# PID.net
KiCad netlist of a schematic drawn in Altium Designer
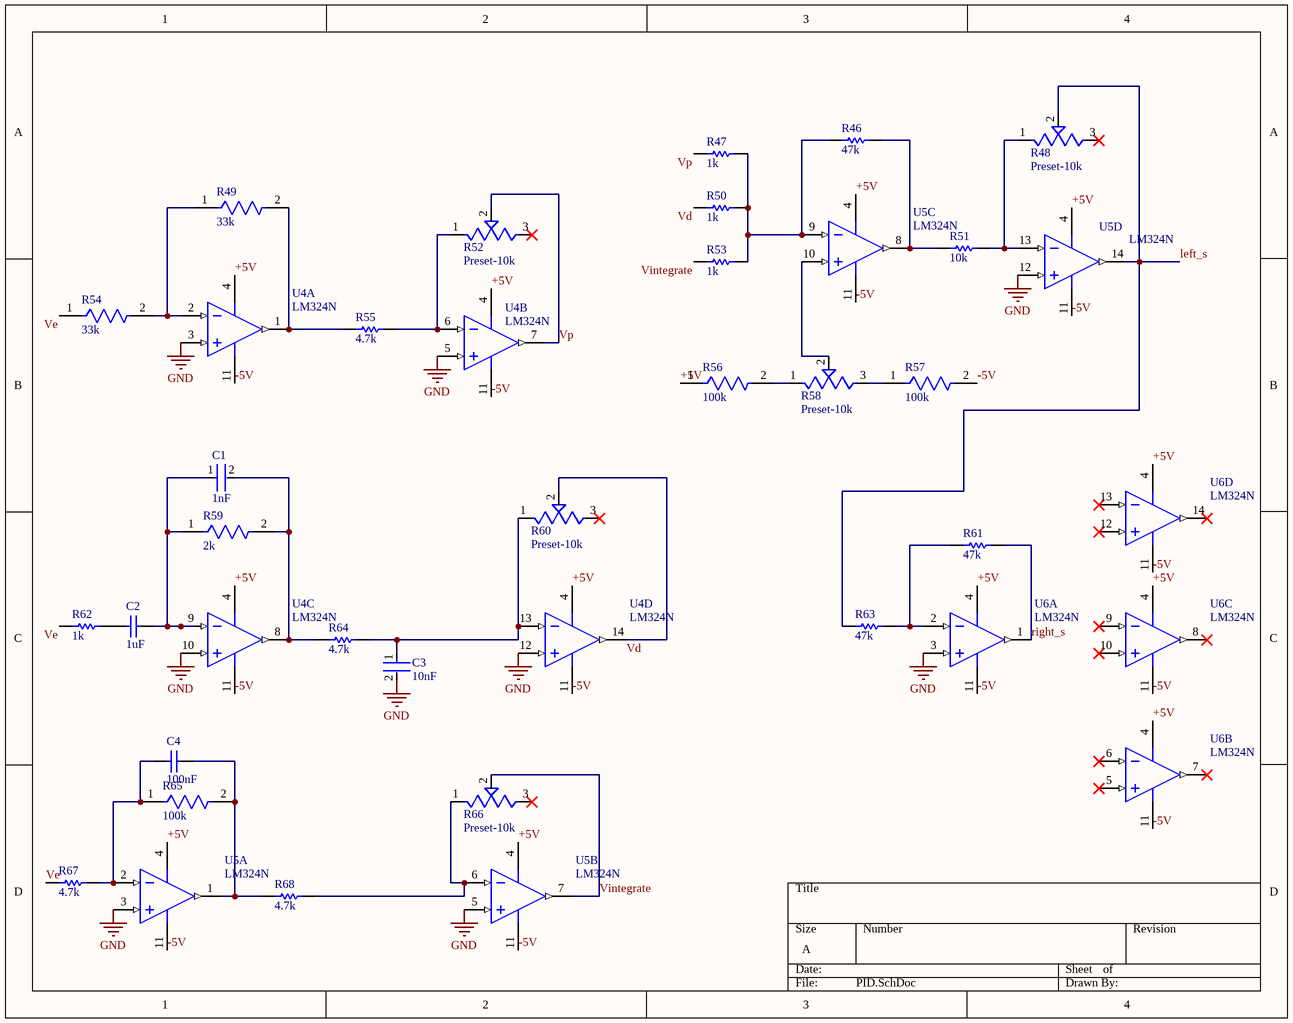
[diagram p0: PID.SchDoc]

(export (version "E")
  (design (tool "Eeschema 10.0.6"))
  (components
    (comp (ref "C1")
      (value "1nF")
      (footprint "FP-CL21-IPC_B")
      (description "CL21 Series 0805 1nF 50V ±10% Tolerance X7R Multilayer Ceramic Chip Capacitor; CL21B102KBANNNC")
      (fields (field (name "TOLERANCE") "10%") (field (name "VOLTAGE") "50V"))
      (libsource (lib "Capacitors") (part "1nF"))
    )
    (comp (ref "C2")
      (value "1uF")
      (footprint "CAPC2013X135X45ML10T25")
      (fields (field (name "MANUFACTURER") "Murata"))
      (libsource (lib "Capacitors") (part "1uF"))
    )
    (comp (ref "C3")
      (value "10nF")
      (footprint "FP-C0805C-DN-MFG")
      (description "CAP CER 10000PF 50V X7R 0805; C0805C103K5RACTU")
      (fields (field (name "MANUFACTURER PART NUMBER") "C0805C103K5RACTU") (field (name "TOLERANCE") "0.1"))
      (libsource (lib "Capacitors") (part "10nF"))
    )
    (comp (ref "C4")
      (value "100nF")
      (footprint "CAPC2013X135X45ML10T25")
      (fields
        (field (name "VOLTAGE") "50V")
        (field (name "TOLERANCE") "10%")
        (field (name "MANUFACTURER") "Murata")
      )
      (libsource (lib "Capacitors") (part "100nF"))
    )
    (comp (ref "R46")
      (value "47k")
      (footprint "RESC2013X60X35NL10T20")
      (fields (field (name "MANUFACTURER") "Yageo"))
      (libsource (lib "Resistors") (part "47k"))
    )
    (comp (ref "R47")
      (value "1k")
      (footprint "RESC2013X60X35ML10T20")
      (fields (field (name "TOLERANCE") "1%") (field (name "MANUFACTURER") "Yageo"))
      (libsource (lib "Resistors") (part "1k"))
    )
    (comp (ref "R48")
      (value "Preset-10k")
      (footprint "TRIM_3306F-1-103")
      (description "TRIMMER - 6MM ROUND, SINGLE-TURN,CERMET, 10K OHMS ¦ Bourns 3306F-1-103")
      (fields (field (name "MF") "Bourns") (field (name "MP") "3306F-1-103"))
      (libsource (lib "3306F-1-103") (part "Preset"))
    )
    (comp (ref "R49")
      (value "33k")
      (footprint "FP-CRCW0805-e3-IPC_B")
      (description "RES Thick Film, 33kΩ, 1%, 0.125W, 100ppm/°C, 0805; CRCW080533K0FKEA")
      (fields (field (name "TOLERANCE") "1%"))
      (libsource (lib "Resistors") (part "33k"))
    )
    (comp (ref "R50")
      (value "1k")
      (footprint "RESC2013X60X35ML10T20")
      (fields (field (name "TOLERANCE") "1%") (field (name "MANUFACTURER") "Yageo"))
      (libsource (lib "Resistors") (part "1k"))
    )
    (comp (ref "R51")
      (value "10k")
      (footprint "RESC2013X60X35NL10T20")
      (fields (field (name "MANUFACTURER") "Yageo"))
      (libsource (lib "Resistors") (part "10k"))
    )
    (comp (ref "R52")
      (value "Preset-10k")
      (footprint "TRIM_3306F-1-103")
      (description "TRIMMER - 6MM ROUND, SINGLE-TURN,CERMET, 10K OHMS ¦ Bourns 3306F-1-103")
      (fields (field (name "MF") "Bourns") (field (name "MP") "3306F-1-103"))
      (libsource (lib "3306F-1-103") (part "Preset"))
    )
    (comp (ref "R53")
      (value "1k")
      (footprint "RESC2013X60X35ML10T20")
      (fields (field (name "TOLERANCE") "1%") (field (name "MANUFACTURER") "Yageo"))
      (libsource (lib "Resistors") (part "1k"))
    )
    (comp (ref "R54")
      (value "33k")
      (footprint "FP-CRCW0805-e3-IPC_B")
      (description "RES Thick Film, 33kΩ, 1%, 0.125W, 100ppm/°C, 0805; CRCW080533K0FKEA")
      (fields (field (name "TOLERANCE") "1%"))
      (libsource (lib "Resistors") (part "33k"))
    )
    (comp (ref "R55")
      (value "4.7k")
      (footprint "YAGO-RC0805_M")
      (fields
        (field (name "TOLERANCE") "+/- 1%")
        (field (name "PARTNUMBER") "RC0805FR-074K7L")
        (field (name "POWER") "0.125 W")
      )
      (libsource (lib "Resistors") (part "4.7k"))
    )
    (comp (ref "R56")
      (value "100k")
      (footprint "FP-RC0805-0_6-IPC_C")
      (description "RES 100K OHM 1% 1/8W 0805; RC0805FR-07100KL")
      (fields (field (name "TOLERANCE") "1%"))
      (libsource (lib "Resistors") (part "100k"))
    )
    (comp (ref "R57")
      (value "100k")
      (footprint "FP-RC0805-0_6-IPC_C")
      (description "RES 100K OHM 1% 1/8W 0805; RC0805FR-07100KL")
      (fields (field (name "TOLERANCE") "1%"))
      (libsource (lib "Resistors") (part "100k"))
    )
    (comp (ref "R58")
      (value "Preset-10k")
      (footprint "TRIM_3306F-1-103")
      (description "TRIMMER - 6MM ROUND, SINGLE-TURN,CERMET, 10K OHMS ¦ Bourns 3306F-1-103")
      (fields (field (name "MF") "Bourns") (field (name "MP") "3306F-1-103"))
      (libsource (lib "3306F-1-103") (part "Preset"))
    )
    (comp (ref "R59")
      (value "2k")
      (footprint "FP-CRCW0805-e3-IPC_B")
      (description "RES Thick Film, 2kΩ, 1%, 0.125W, 100ppm/°C, 0805; CRCW08052K00FKEA")
      (fields (field (name "TOLERANCE") "1%"))
      (libsource (lib "Resistors") (part "2k"))
    )
    (comp (ref "R60")
      (value "Preset-10k")
      (footprint "TRIM_3306F-1-103")
      (description "TRIMMER - 6MM ROUND, SINGLE-TURN,CERMET, 10K OHMS ¦ Bourns 3306F-1-103")
      (fields (field (name "MF") "Bourns") (field (name "MP") "3306F-1-103"))
      (libsource (lib "3306F-1-103") (part "Preset"))
    )
    (comp (ref "R61")
      (value "47k")
      (footprint "RESC2013X60X35NL10T20")
      (fields (field (name "MANUFACTURER") "Yageo"))
      (libsource (lib "Resistors") (part "47k"))
    )
    (comp (ref "R62")
      (value "1k")
      (footprint "RESC2013X60X35ML10T20")
      (fields (field (name "TOLERANCE") "1%") (field (name "MANUFACTURER") "Yageo"))
      (libsource (lib "Resistors") (part "1k"))
    )
    (comp (ref "R63")
      (value "47k")
      (footprint "RESC2013X60X35NL10T20")
      (fields (field (name "MANUFACTURER") "Yageo"))
      (libsource (lib "Resistors") (part "47k"))
    )
    (comp (ref "R64")
      (value "4.7k")
      (footprint "YAGO-RC0805_M")
      (fields
        (field (name "TOLERANCE") "+/- 1%")
        (field (name "PARTNUMBER") "RC0805FR-074K7L")
        (field (name "POWER") "0.125 W")
      )
      (libsource (lib "Resistors") (part "4.7k"))
    )
    (comp (ref "R65")
      (value "100k")
      (footprint "FP-RC0805-0_6-IPC_C")
      (description "RES 100K OHM 1% 1/8W 0805; RC0805FR-07100KL")
      (fields (field (name "TOLERANCE") "1%"))
      (libsource (lib "Resistors") (part "100k"))
    )
    (comp (ref "R66")
      (value "Preset-10k")
      (footprint "TRIM_3306F-1-103")
      (description "TRIMMER - 6MM ROUND, SINGLE-TURN,CERMET, 10K OHMS ¦ Bourns 3306F-1-103")
      (fields (field (name "MF") "Bourns") (field (name "MP") "3306F-1-103"))
      (libsource (lib "3306F-1-103") (part "Preset"))
    )
    (comp (ref "R67")
      (value "4.7k")
      (footprint "YAGO-RC0805_M")
      (fields
        (field (name "TOLERANCE") "+/- 1%")
        (field (name "PARTNUMBER") "RC0805FR-074K7L")
        (field (name "POWER") "0.125 W")
      )
      (libsource (lib "Resistors") (part "4.7k"))
    )
    (comp (ref "R68")
      (value "4.7k")
      (footprint "YAGO-RC0805_M")
      (fields
        (field (name "TOLERANCE") "+/- 1%")
        (field (name "PARTNUMBER") "RC0805FR-074K7L")
        (field (name "POWER") "0.125 W")
      )
      (libsource (lib "Resistors") (part "4.7k"))
    )
    (comp (ref "U4")
      (value "LM324N")
      (footprint "N0014A")
      (description "Low Power Quad Operational Amplifier, 14-pin MDIP")
      (fields (field (name "MANUFACTURER") "Texas Instruments"))
      (libsource (lib "ICs") (part "LM324N"))
    )
    (comp (ref "U5")
      (value "LM324N")
      (footprint "N0014A")
      (description "Low Power Quad Operational Amplifier, 14-pin MDIP")
      (fields (field (name "MANUFACTURER") "Texas Instruments"))
      (libsource (lib "ICs") (part "LM324N"))
    )
    (comp (ref "U6")
      (value "LM324N")
      (footprint "N0014A")
      (description "Low Power Quad Operational Amplifier, 14-pin MDIP")
      (fields (field (name "MANUFACTURER") "Texas Instruments"))
      (libsource (lib "ICs") (part "LM324N"))
    )
  )
  (nets
    (net (code "1") (name "/+5V") (class "Default")
      (node (ref "R56") (pin "1") (pinfunction "1_1") (pintype "passive"))
      (node (ref "U4") (pin "4") (pinfunction "V+_4") (pintype "power_in"))
      (node (ref "U5") (pin "4") (pinfunction "V+_4") (pintype "power_in"))
      (node (ref "U6") (pin "4") (pinfunction "V+_4") (pintype "power_in"))
    )
    (net (code "2") (name "/-5V") (class "Default")
      (node (ref "R57") (pin "2") (pinfunction "2_2") (pintype "passive"))
      (node (ref "U4") (pin "11") (pinfunction "GND_11") (pintype "power_in"))
      (node (ref "U5") (pin "11") (pinfunction "GND_11") (pintype "power_in"))
      (node (ref "U6") (pin "11") (pinfunction "GND_11") (pintype "power_in"))
    )
    (net (code "3") (name "/Vd") (class "Default")
      (node (ref "R50") (pin "1") (pinfunction "1_1") (pintype "passive"))
      (node (ref "R60") (pin "2") (pinfunction "W_2") (pintype "passive"))
      (node (ref "U4") (pin "14") (pinfunction "OUT4_14") (pintype "output"))
    )
    (net (code "4") (name "/Ve") (class "Default")
      (node (ref "R54") (pin "1") (pinfunction "1_1") (pintype "passive"))
      (node (ref "R62") (pin "1") (pinfunction "1_1") (pintype "passive"))
      (node (ref "R67") (pin "1") (pinfunction "1_1") (pintype "passive"))
    )
    (net (code "5") (name "/Vintegrate") (class "Default")
      (node (ref "R53") (pin "1") (pinfunction "1_1") (pintype "passive"))
      (node (ref "R66") (pin "2") (pinfunction "W_2") (pintype "passive"))
      (node (ref "U5") (pin "7") (pinfunction "OUT2_7") (pintype "output"))
    )
    (net (code "6") (name "/Vp") (class "Default")
      (node (ref "R47") (pin "1") (pinfunction "1_1") (pintype "passive"))
      (node (ref "R52") (pin "2") (pinfunction "W_2") (pintype "passive"))
      (node (ref "U4") (pin "7") (pinfunction "OUT2_7") (pintype "output"))
    )
    (net (code "7") (name "/left_s") (class "Default")
      (node (ref "R48") (pin "2") (pinfunction "W_2") (pintype "passive"))
      (node (ref "R63") (pin "1") (pinfunction "1_1") (pintype "passive"))
      (node (ref "U5") (pin "14") (pinfunction "OUT4_14") (pintype "output"))
    )
    (net (code "8") (name "/right_s") (class "Default")
      (node (ref "R61") (pin "2") (pinfunction "2_2") (pintype "passive"))
      (node (ref "U6") (pin "1") (pinfunction "OUT1_1") (pintype "output"))
    )
    (net (code "9") (name "GND") (class "Default")
      (node (ref "C3") (pin "2") (pinfunction "2_2") (pintype "passive"))
      (node (ref "U4") (pin "10") (pinfunction "IN3+_10") (pintype "input"))
      (node (ref "U4") (pin "12") (pinfunction "IN4+_12") (pintype "input"))
      (node (ref "U4") (pin "3") (pinfunction "IN1+_3") (pintype "input"))
      (node (ref "U4") (pin "5") (pinfunction "IN2+_5") (pintype "input"))
      (node (ref "U5") (pin "12") (pinfunction "IN4+_12") (pintype "input"))
      (node (ref "U5") (pin "3") (pinfunction "IN1+_3") (pintype "input"))
      (node (ref "U5") (pin "5") (pinfunction "IN2+_5") (pintype "input"))
      (node (ref "U6") (pin "3") (pinfunction "IN1+_3") (pintype "input"))
    )
    (net (code "10") (name "Net-(C2-Pad1)") (class "Default")
      (node (ref "C2") (pin "1") (pinfunction "1_1") (pintype "passive"))
      (node (ref "R62") (pin "2") (pinfunction "2_2") (pintype "passive"))
    )
    (net (code "11") (name "Net-(R48-CCW)") (class "Default")
      (node (ref "R48") (pin "1") (pinfunction "CCW_1") (pintype "passive"))
      (node (ref "R51") (pin "2") (pinfunction "2_2") (pintype "passive"))
      (node (ref "U5") (pin "13") (pinfunction "IN4-_13") (pintype "input"))
    )
    (net (code "12") (name "Net-(R52-CCW)") (class "Default")
      (node (ref "R52") (pin "1") (pinfunction "CCW_1") (pintype "passive"))
      (node (ref "R55") (pin "2") (pinfunction "2_2") (pintype "passive"))
      (node (ref "U4") (pin "6") (pinfunction "IN2-_6") (pintype "input"))
    )
    (net (code "13") (name "Net-(R58-CCW)") (class "Default")
      (node (ref "R56") (pin "2") (pinfunction "2_2") (pintype "passive"))
      (node (ref "R58") (pin "1") (pinfunction "CCW_1") (pintype "passive"))
    )
    (net (code "14") (name "Net-(R58-CW)") (class "Default")
      (node (ref "R57") (pin "1") (pinfunction "1_1") (pintype "passive"))
      (node (ref "R58") (pin "3") (pinfunction "CW_3") (pintype "passive"))
    )
    (net (code "15") (name "Net-(R58-W)") (class "Default")
      (node (ref "R58") (pin "2") (pinfunction "W_2") (pintype "passive"))
      (node (ref "U5") (pin "10") (pinfunction "IN3+_10") (pintype "input"))
    )
    (net (code "16") (name "Net-(R60-CCW)") (class "Default")
      (node (ref "C3") (pin "1") (pinfunction "1_1") (pintype "passive"))
      (node (ref "R60") (pin "1") (pinfunction "CCW_1") (pintype "passive"))
      (node (ref "R64") (pin "2") (pinfunction "2_2") (pintype "passive"))
      (node (ref "U4") (pin "13") (pinfunction "IN4-_13") (pintype "input"))
    )
    (net (code "17") (name "Net-(R66-CCW)") (class "Default")
      (node (ref "R66") (pin "1") (pinfunction "CCW_1") (pintype "passive"))
      (node (ref "R68") (pin "2") (pinfunction "2_2") (pintype "passive"))
      (node (ref "U5") (pin "6") (pinfunction "IN2-_6") (pintype "input"))
    )
    (net (code "18") (name "Net-(U4A-IN1-)") (class "Default")
      (node (ref "R49") (pin "1") (pinfunction "1_1") (pintype "passive"))
      (node (ref "R54") (pin "2") (pinfunction "2_2") (pintype "passive"))
      (node (ref "U4") (pin "2") (pinfunction "IN1-_2") (pintype "input"))
    )
    (net (code "19") (name "Net-(U4A-OUT1)") (class "Default")
      (node (ref "R49") (pin "2") (pinfunction "2_2") (pintype "passive"))
      (node (ref "R55") (pin "1") (pinfunction "1_1") (pintype "passive"))
      (node (ref "U4") (pin "1") (pinfunction "OUT1_1") (pintype "output"))
    )
    (net (code "20") (name "Net-(U4C-IN3-)") (class "Default")
      (node (ref "C1") (pin "1") (pinfunction "1_1") (pintype "passive"))
      (node (ref "C2") (pin "2") (pinfunction "2_2") (pintype "passive"))
      (node (ref "R59") (pin "1") (pinfunction "1_1") (pintype "passive"))
      (node (ref "U4") (pin "9") (pinfunction "IN3-_9") (pintype "input"))
    )
    (net (code "21") (name "Net-(U4C-OUT3)") (class "Default")
      (node (ref "C1") (pin "2") (pinfunction "2_2") (pintype "passive"))
      (node (ref "R59") (pin "2") (pinfunction "2_2") (pintype "passive"))
      (node (ref "R64") (pin "1") (pinfunction "1_1") (pintype "passive"))
      (node (ref "U4") (pin "8") (pinfunction "OUT3_8") (pintype "output"))
    )
    (net (code "22") (name "Net-(U5A-IN1-)") (class "Default")
      (node (ref "C4") (pin "1") (pinfunction "1_1") (pintype "passive"))
      (node (ref "R65") (pin "1") (pinfunction "1_1") (pintype "passive"))
      (node (ref "R67") (pin "2") (pinfunction "2_2") (pintype "passive"))
      (node (ref "U5") (pin "2") (pinfunction "IN1-_2") (pintype "input"))
    )
    (net (code "23") (name "Net-(U5A-OUT1)") (class "Default")
      (node (ref "C4") (pin "2") (pinfunction "2_2") (pintype "passive"))
      (node (ref "R65") (pin "2") (pinfunction "2_2") (pintype "passive"))
      (node (ref "R68") (pin "1") (pinfunction "1_1") (pintype "passive"))
      (node (ref "U5") (pin "1") (pinfunction "OUT1_1") (pintype "output"))
    )
    (net (code "24") (name "Net-(U5C-IN3-)") (class "Default")
      (node (ref "R46") (pin "1") (pinfunction "1_1") (pintype "passive"))
      (node (ref "R47") (pin "2") (pinfunction "2_2") (pintype "passive"))
      (node (ref "R50") (pin "2") (pinfunction "2_2") (pintype "passive"))
      (node (ref "R53") (pin "2") (pinfunction "2_2") (pintype "passive"))
      (node (ref "U5") (pin "9") (pinfunction "IN3-_9") (pintype "input"))
    )
    (net (code "25") (name "Net-(U5C-OUT3)") (class "Default")
      (node (ref "R46") (pin "2") (pinfunction "2_2") (pintype "passive"))
      (node (ref "R51") (pin "1") (pinfunction "1_1") (pintype "passive"))
      (node (ref "U5") (pin "8") (pinfunction "OUT3_8") (pintype "output"))
    )
    (net (code "26") (name "Net-(U6A-IN1-)") (class "Default")
      (node (ref "R61") (pin "1") (pinfunction "1_1") (pintype "passive"))
      (node (ref "R63") (pin "2") (pinfunction "2_2") (pintype "passive"))
      (node (ref "U6") (pin "2") (pinfunction "IN1-_2") (pintype "input"))
    )
    (net (code "27") (name "unconnected-(R48-CW-Pad3)") (class "Default")
      (node (ref "R48") (pin "3") (pinfunction "CW_3") (pintype "passive+no_connect"))
    )
    (net (code "28") (name "unconnected-(R52-CW-Pad3)") (class "Default")
      (node (ref "R52") (pin "3") (pinfunction "CW_3") (pintype "passive+no_connect"))
    )
    (net (code "29") (name "unconnected-(R60-CW-Pad3)") (class "Default")
      (node (ref "R60") (pin "3") (pinfunction "CW_3") (pintype "passive+no_connect"))
    )
    (net (code "30") (name "unconnected-(R66-CW-Pad3)") (class "Default")
      (node (ref "R66") (pin "3") (pinfunction "CW_3") (pintype "passive+no_connect"))
    )
    (net (code "31") (name "unconnected-(U6B-IN2+-Pad5)") (class "Default")
      (node (ref "U6") (pin "5") (pinfunction "IN2+_5") (pintype "input+no_connect"))
    )
    (net (code "32") (name "unconnected-(U6B-IN2--Pad6)") (class "Default")
      (node (ref "U6") (pin "6") (pinfunction "IN2-_6") (pintype "input+no_connect"))
    )
    (net (code "33") (name "unconnected-(U6B-OUT2-Pad7)") (class "Default")
      (node (ref "U6") (pin "7") (pinfunction "OUT2_7") (pintype "output+no_connect"))
    )
    (net (code "34") (name "unconnected-(U6C-IN3+-Pad10)") (class "Default")
      (node (ref "U6") (pin "10") (pinfunction "IN3+_10") (pintype "input+no_connect"))
    )
    (net (code "35") (name "unconnected-(U6C-IN3--Pad9)") (class "Default")
      (node (ref "U6") (pin "9") (pinfunction "IN3-_9") (pintype "input+no_connect"))
    )
    (net (code "36") (name "unconnected-(U6C-OUT3-Pad8)") (class "Default")
      (node (ref "U6") (pin "8") (pinfunction "OUT3_8") (pintype "output+no_connect"))
    )
    (net (code "37") (name "unconnected-(U6D-IN4+-Pad12)") (class "Default")
      (node (ref "U6") (pin "12") (pinfunction "IN4+_12") (pintype "input+no_connect"))
    )
    (net (code "38") (name "unconnected-(U6D-IN4--Pad13)") (class "Default")
      (node (ref "U6") (pin "13") (pinfunction "IN4-_13") (pintype "input+no_connect"))
    )
    (net (code "39") (name "unconnected-(U6D-OUT4-Pad14)") (class "Default")
      (node (ref "U6") (pin "14") (pinfunction "OUT4_14") (pintype "output+no_connect"))
    )
  )
)
